# usb-current-meter-8x.net
KiCad netlist of a schematic drawn in EAGLE
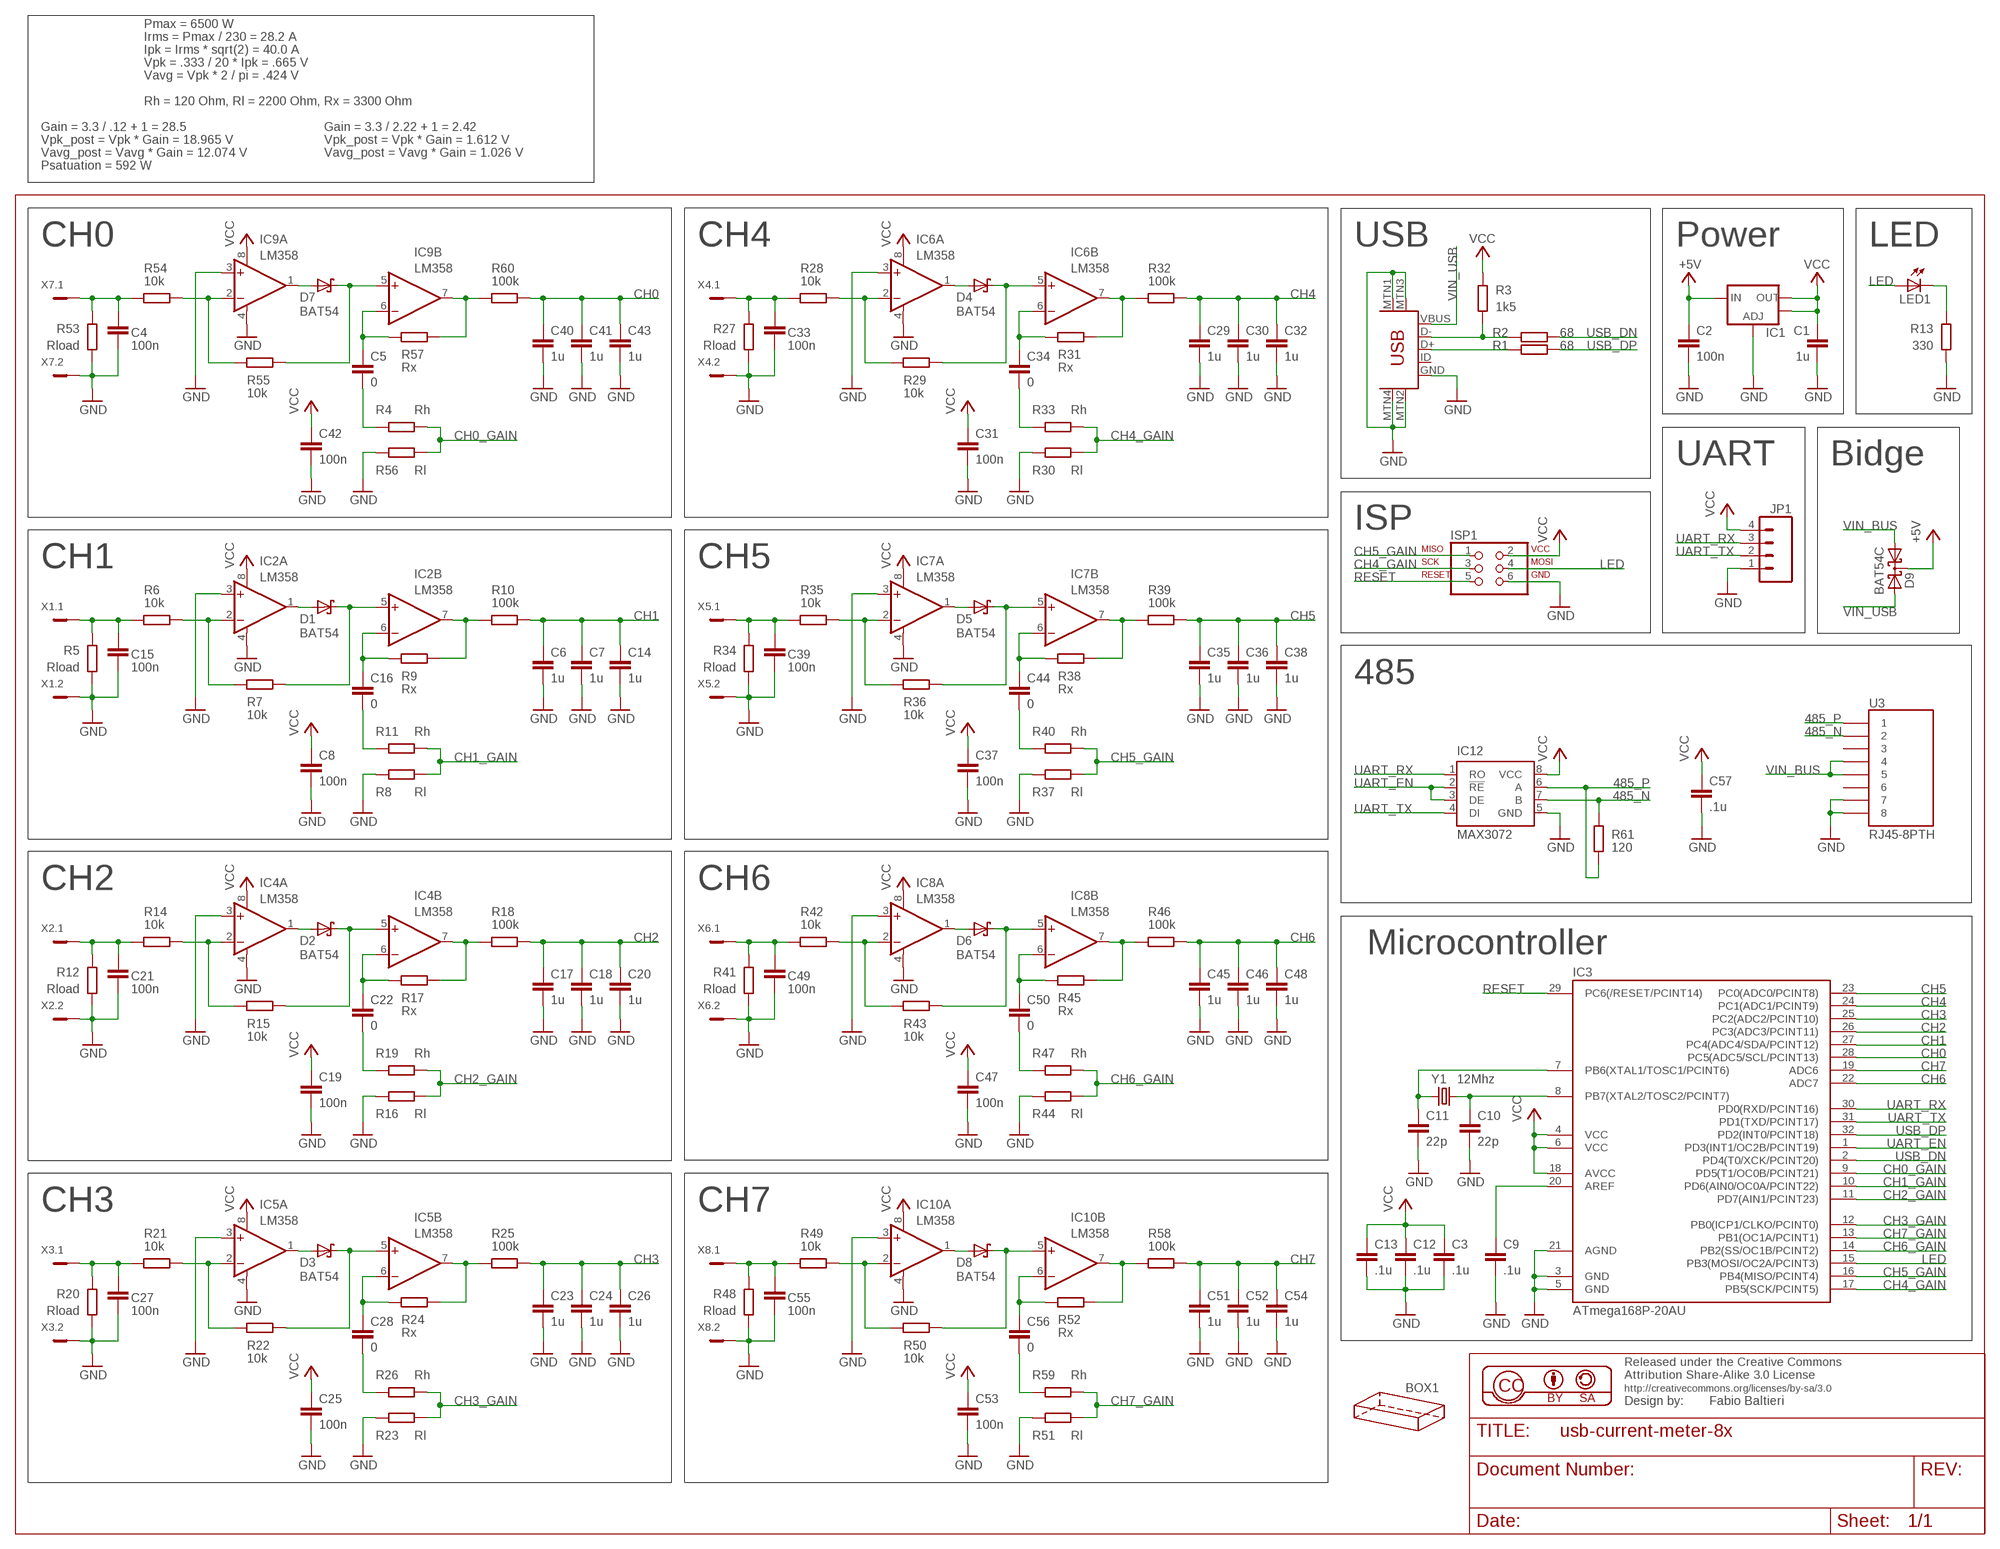
[diagram p0: schematic, sheet 1]

(export (version "E")
  (design (tool "Eeschema 10.0.6"))
  (components
    (comp (ref "BOX1")
      (value "HAMMOND-BOX-XXA")
      (footprint "eagle-import:1591XXA")
      (libsource (lib "eagle-import") (part "HAMMOND-BOX-XXA"))
    )
    (comp (ref "C1")
      (value "1u")
      (footprint "eagle-import:C0805")
      (libsource (lib "eagle-import") (part "C-EUC0805"))
    )
    (comp (ref "C2")
      (value "100n")
      (footprint "eagle-import:C0805")
      (libsource (lib "eagle-import") (part "C-EUC0805"))
    )
    (comp (ref "C3")
      (value ".1u")
      (footprint "eagle-import:C0805")
      (libsource (lib "eagle-import") (part "C-EUC0805"))
    )
    (comp (ref "C4")
      (value "100n")
      (footprint "eagle-import:C0805")
      (libsource (lib "eagle-import") (part "C-EUC0805"))
    )
    (comp (ref "C5")
      (value "0")
      (footprint "eagle-import:C0805")
      (libsource (lib "eagle-import") (part "C-EUC0805"))
    )
    (comp (ref "C6")
      (value "1u")
      (footprint "eagle-import:C0805")
      (libsource (lib "eagle-import") (part "C-EUC0805"))
    )
    (comp (ref "C7")
      (value "1u")
      (footprint "eagle-import:C0805")
      (libsource (lib "eagle-import") (part "C-EUC0805"))
    )
    (comp (ref "C8")
      (value "100n")
      (footprint "eagle-import:C0805")
      (libsource (lib "eagle-import") (part "C-EUC0805"))
    )
    (comp (ref "C9")
      (value ".1u")
      (footprint "eagle-import:C0805")
      (libsource (lib "eagle-import") (part "C-EUC0805"))
    )
    (comp (ref "C10")
      (value "22p")
      (footprint "eagle-import:C0805")
      (libsource (lib "eagle-import") (part "C-EUC0805"))
    )
    (comp (ref "C11")
      (value "22p")
      (footprint "eagle-import:C0805")
      (libsource (lib "eagle-import") (part "C-EUC0805"))
    )
    (comp (ref "C12")
      (value ".1u")
      (footprint "eagle-import:C0805")
      (libsource (lib "eagle-import") (part "C-EUC0805"))
    )
    (comp (ref "C13")
      (value ".1u")
      (footprint "eagle-import:C0805")
      (libsource (lib "eagle-import") (part "C-EUC0805"))
    )
    (comp (ref "C14")
      (value "1u")
      (footprint "eagle-import:C0805")
      (libsource (lib "eagle-import") (part "C-EUC0805"))
    )
    (comp (ref "C15")
      (value "100n")
      (footprint "eagle-import:C0805")
      (libsource (lib "eagle-import") (part "C-EUC0805"))
    )
    (comp (ref "C16")
      (value "0")
      (footprint "eagle-import:C0805")
      (libsource (lib "eagle-import") (part "C-EUC0805"))
    )
    (comp (ref "C17")
      (value "1u")
      (footprint "eagle-import:C0805")
      (libsource (lib "eagle-import") (part "C-EUC0805"))
    )
    (comp (ref "C18")
      (value "1u")
      (footprint "eagle-import:C0805")
      (libsource (lib "eagle-import") (part "C-EUC0805"))
    )
    (comp (ref "C19")
      (value "100n")
      (footprint "eagle-import:C0805")
      (libsource (lib "eagle-import") (part "C-EUC0805"))
    )
    (comp (ref "C20")
      (value "1u")
      (footprint "eagle-import:C0805")
      (libsource (lib "eagle-import") (part "C-EUC0805"))
    )
    (comp (ref "C21")
      (value "100n")
      (footprint "eagle-import:C0805")
      (libsource (lib "eagle-import") (part "C-EUC0805"))
    )
    (comp (ref "C22")
      (value "0")
      (footprint "eagle-import:C0805")
      (libsource (lib "eagle-import") (part "C-EUC0805"))
    )
    (comp (ref "C23")
      (value "1u")
      (footprint "eagle-import:C0805")
      (libsource (lib "eagle-import") (part "C-EUC0805"))
    )
    (comp (ref "C24")
      (value "1u")
      (footprint "eagle-import:C0805")
      (libsource (lib "eagle-import") (part "C-EUC0805"))
    )
    (comp (ref "C25")
      (value "100n")
      (footprint "eagle-import:C0805")
      (libsource (lib "eagle-import") (part "C-EUC0805"))
    )
    (comp (ref "C26")
      (value "1u")
      (footprint "eagle-import:C0805")
      (libsource (lib "eagle-import") (part "C-EUC0805"))
    )
    (comp (ref "C27")
      (value "100n")
      (footprint "eagle-import:C0805")
      (libsource (lib "eagle-import") (part "C-EUC0805"))
    )
    (comp (ref "C28")
      (value "0")
      (footprint "eagle-import:C0805")
      (libsource (lib "eagle-import") (part "C-EUC0805"))
    )
    (comp (ref "C29")
      (value "1u")
      (footprint "eagle-import:C0805")
      (libsource (lib "eagle-import") (part "C-EUC0805"))
    )
    (comp (ref "C30")
      (value "1u")
      (footprint "eagle-import:C0805")
      (libsource (lib "eagle-import") (part "C-EUC0805"))
    )
    (comp (ref "C31")
      (value "100n")
      (footprint "eagle-import:C0805")
      (libsource (lib "eagle-import") (part "C-EUC0805"))
    )
    (comp (ref "C32")
      (value "1u")
      (footprint "eagle-import:C0805")
      (libsource (lib "eagle-import") (part "C-EUC0805"))
    )
    (comp (ref "C33")
      (value "100n")
      (footprint "eagle-import:C0805")
      (libsource (lib "eagle-import") (part "C-EUC0805"))
    )
    (comp (ref "C34")
      (value "0")
      (footprint "eagle-import:C0805")
      (libsource (lib "eagle-import") (part "C-EUC0805"))
    )
    (comp (ref "C35")
      (value "1u")
      (footprint "eagle-import:C0805")
      (libsource (lib "eagle-import") (part "C-EUC0805"))
    )
    (comp (ref "C36")
      (value "1u")
      (footprint "eagle-import:C0805")
      (libsource (lib "eagle-import") (part "C-EUC0805"))
    )
    (comp (ref "C37")
      (value "100n")
      (footprint "eagle-import:C0805")
      (libsource (lib "eagle-import") (part "C-EUC0805"))
    )
    (comp (ref "C38")
      (value "1u")
      (footprint "eagle-import:C0805")
      (libsource (lib "eagle-import") (part "C-EUC0805"))
    )
    (comp (ref "C39")
      (value "100n")
      (footprint "eagle-import:C0805")
      (libsource (lib "eagle-import") (part "C-EUC0805"))
    )
    (comp (ref "C40")
      (value "1u")
      (footprint "eagle-import:C0805")
      (libsource (lib "eagle-import") (part "C-EUC0805"))
    )
    (comp (ref "C41")
      (value "1u")
      (footprint "eagle-import:C0805")
      (libsource (lib "eagle-import") (part "C-EUC0805"))
    )
    (comp (ref "C42")
      (value "100n")
      (footprint "eagle-import:C0805")
      (libsource (lib "eagle-import") (part "C-EUC0805"))
    )
    (comp (ref "C43")
      (value "1u")
      (footprint "eagle-import:C0805")
      (libsource (lib "eagle-import") (part "C-EUC0805"))
    )
    (comp (ref "C44")
      (value "0")
      (footprint "eagle-import:C0805")
      (libsource (lib "eagle-import") (part "C-EUC0805"))
    )
    (comp (ref "C45")
      (value "1u")
      (footprint "eagle-import:C0805")
      (libsource (lib "eagle-import") (part "C-EUC0805"))
    )
    (comp (ref "C46")
      (value "1u")
      (footprint "eagle-import:C0805")
      (libsource (lib "eagle-import") (part "C-EUC0805"))
    )
    (comp (ref "C47")
      (value "100n")
      (footprint "eagle-import:C0805")
      (libsource (lib "eagle-import") (part "C-EUC0805"))
    )
    (comp (ref "C48")
      (value "1u")
      (footprint "eagle-import:C0805")
      (libsource (lib "eagle-import") (part "C-EUC0805"))
    )
    (comp (ref "C49")
      (value "100n")
      (footprint "eagle-import:C0805")
      (libsource (lib "eagle-import") (part "C-EUC0805"))
    )
    (comp (ref "C50")
      (value "0")
      (footprint "eagle-import:C0805")
      (libsource (lib "eagle-import") (part "C-EUC0805"))
    )
    (comp (ref "C51")
      (value "1u")
      (footprint "eagle-import:C0805")
      (libsource (lib "eagle-import") (part "C-EUC0805"))
    )
    (comp (ref "C52")
      (value "1u")
      (footprint "eagle-import:C0805")
      (libsource (lib "eagle-import") (part "C-EUC0805"))
    )
    (comp (ref "C53")
      (value "100n")
      (footprint "eagle-import:C0805")
      (libsource (lib "eagle-import") (part "C-EUC0805"))
    )
    (comp (ref "C54")
      (value "1u")
      (footprint "eagle-import:C0805")
      (libsource (lib "eagle-import") (part "C-EUC0805"))
    )
    (comp (ref "C55")
      (value "100n")
      (footprint "eagle-import:C0805")
      (libsource (lib "eagle-import") (part "C-EUC0805"))
    )
    (comp (ref "C56")
      (value "0")
      (footprint "eagle-import:C0805")
      (libsource (lib "eagle-import") (part "C-EUC0805"))
    )
    (comp (ref "C57")
      (value ".1u")
      (footprint "eagle-import:C0805")
      (libsource (lib "eagle-import") (part "C-EUC0805"))
    )
    (comp (ref "D1")
      (value "BAT54")
      (footprint "eagle-import:SOT23")
      (libsource (lib "eagle-import") (part "BAT54"))
    )
    (comp (ref "D2")
      (value "BAT54")
      (footprint "eagle-import:SOT23")
      (libsource (lib "eagle-import") (part "BAT54"))
    )
    (comp (ref "D3")
      (value "BAT54")
      (footprint "eagle-import:SOT23")
      (libsource (lib "eagle-import") (part "BAT54"))
    )
    (comp (ref "D4")
      (value "BAT54")
      (footprint "eagle-import:SOT23")
      (libsource (lib "eagle-import") (part "BAT54"))
    )
    (comp (ref "D5")
      (value "BAT54")
      (footprint "eagle-import:SOT23")
      (libsource (lib "eagle-import") (part "BAT54"))
    )
    (comp (ref "D6")
      (value "BAT54")
      (footprint "eagle-import:SOT23")
      (libsource (lib "eagle-import") (part "BAT54"))
    )
    (comp (ref "D7")
      (value "BAT54")
      (footprint "eagle-import:SOT23")
      (libsource (lib "eagle-import") (part "BAT54"))
    )
    (comp (ref "D8")
      (value "BAT54")
      (footprint "eagle-import:SOT23")
      (libsource (lib "eagle-import") (part "BAT54"))
    )
    (comp (ref "D9")
      (value "BAT54C")
      (footprint "eagle-import:SOT23")
      (libsource (lib "eagle-import") (part "BAT54C"))
    )
    (comp (ref "IC1")
      (value "V_REG_LM1117SOT223")
      (footprint "eagle-import:SOT223")
      (libsource (lib "eagle-import") (part "V_REG_LM1117SOT223"))
    )
    (comp (ref "IC2")
      (value "LM358")
      (footprint "eagle-import:SO08")
      (fields (field (name "MF") "TEXAS INSTRUMENTS") (field (name "MPN") "OPA2234U"))
      (libsource (lib "eagle-import") (part "OPA2234U"))
    )
    (comp (ref "IC3")
      (value "ATmega168P-20AU")
      (footprint "eagle-import:TQFP32-08")
      (libsource (lib "eagle-import") (part "MEGA48/88/168-AU"))
    )
    (comp (ref "IC4")
      (value "LM358")
      (footprint "eagle-import:SO08")
      (fields (field (name "MF") "TEXAS INSTRUMENTS") (field (name "MPN") "OPA2234U"))
      (libsource (lib "eagle-import") (part "OPA2234U"))
    )
    (comp (ref "IC5")
      (value "LM358")
      (footprint "eagle-import:SO08")
      (fields (field (name "MF") "TEXAS INSTRUMENTS") (field (name "MPN") "OPA2234U"))
      (libsource (lib "eagle-import") (part "OPA2234U"))
    )
    (comp (ref "IC6")
      (value "LM358")
      (footprint "eagle-import:SO08")
      (fields (field (name "MF") "TEXAS INSTRUMENTS") (field (name "MPN") "OPA2234U"))
      (libsource (lib "eagle-import") (part "OPA2234U"))
    )
    (comp (ref "IC7")
      (value "LM358")
      (footprint "eagle-import:SO08")
      (fields (field (name "MF") "TEXAS INSTRUMENTS") (field (name "MPN") "OPA2234U"))
      (libsource (lib "eagle-import") (part "OPA2234U"))
    )
    (comp (ref "IC8")
      (value "LM358")
      (footprint "eagle-import:SO08")
      (fields (field (name "MF") "TEXAS INSTRUMENTS") (field (name "MPN") "OPA2234U"))
      (libsource (lib "eagle-import") (part "OPA2234U"))
    )
    (comp (ref "IC9")
      (value "LM358")
      (footprint "eagle-import:SO08")
      (fields (field (name "MF") "TEXAS INSTRUMENTS") (field (name "MPN") "OPA2234U"))
      (libsource (lib "eagle-import") (part "OPA2234U"))
    )
    (comp (ref "IC10")
      (value "LM358")
      (footprint "eagle-import:SO08")
      (fields (field (name "MF") "TEXAS INSTRUMENTS") (field (name "MPN") "OPA2234U"))
      (libsource (lib "eagle-import") (part "OPA2234U"))
    )
    (comp (ref "IC12")
      (value "MAX3072")
      (footprint "eagle-import:SOIC8")
      (libsource (lib "eagle-import") (part "LTC485S"))
    )
    (comp (ref "ISP1")
      (value "ISP-AVR910PTH")
      (footprint "eagle-import:2X03")
      (libsource (lib "eagle-import") (part "ISP-AVR910PTH"))
    )
    (comp (ref "JP1")
      (value "M04PTH")
      (footprint "eagle-import:1X04")
      (libsource (lib "eagle-import") (part "M04PTH"))
    )
    (comp (ref "LED1")
      (value "LEDSML0805")
      (footprint "eagle-import:SML0805")
      (libsource (lib "eagle-import") (part "LEDSML0805"))
    )
    (comp (ref "R1")
      (value "68")
      (footprint "eagle-import:R0603")
      (libsource (lib "eagle-import") (part "R-EU_R0603"))
    )
    (comp (ref "R2")
      (value "68")
      (footprint "eagle-import:R0603")
      (libsource (lib "eagle-import") (part "R-EU_R0603"))
    )
    (comp (ref "R3")
      (value "1k5")
      (footprint "eagle-import:R0603")
      (libsource (lib "eagle-import") (part "R-EU_R0603"))
    )
    (comp (ref "R4")
      (value "Rh")
      (footprint "eagle-import:R0603")
      (libsource (lib "eagle-import") (part "R-EU_R0603"))
    )
    (comp (ref "R5")
      (value "Rload")
      (footprint "eagle-import:R0805")
      (libsource (lib "eagle-import") (part "R-EU_R0805"))
    )
    (comp (ref "R6")
      (value "10k")
      (footprint "eagle-import:R0603")
      (libsource (lib "eagle-import") (part "R-EU_R0603"))
    )
    (comp (ref "R7")
      (value "10k")
      (footprint "eagle-import:R0603")
      (libsource (lib "eagle-import") (part "R-EU_R0603"))
    )
    (comp (ref "R8")
      (value "Rl")
      (footprint "eagle-import:R0603")
      (libsource (lib "eagle-import") (part "R-EU_R0603"))
    )
    (comp (ref "R9")
      (value "Rx")
      (footprint "eagle-import:R0603")
      (libsource (lib "eagle-import") (part "R-EU_R0603"))
    )
    (comp (ref "R10")
      (value "100k")
      (footprint "eagle-import:R0603")
      (libsource (lib "eagle-import") (part "R-EU_R0603"))
    )
    (comp (ref "R11")
      (value "Rh")
      (footprint "eagle-import:R0603")
      (libsource (lib "eagle-import") (part "R-EU_R0603"))
    )
    (comp (ref "R12")
      (value "Rload")
      (footprint "eagle-import:R0805")
      (libsource (lib "eagle-import") (part "R-EU_R0805"))
    )
    (comp (ref "R13")
      (value "330")
      (footprint "eagle-import:R0603")
      (libsource (lib "eagle-import") (part "R-EU_R0603"))
    )
    (comp (ref "R14")
      (value "10k")
      (footprint "eagle-import:R0603")
      (libsource (lib "eagle-import") (part "R-EU_R0603"))
    )
    (comp (ref "R15")
      (value "10k")
      (footprint "eagle-import:R0603")
      (libsource (lib "eagle-import") (part "R-EU_R0603"))
    )
    (comp (ref "R16")
      (value "Rl")
      (footprint "eagle-import:R0603")
      (libsource (lib "eagle-import") (part "R-EU_R0603"))
    )
    (comp (ref "R17")
      (value "Rx")
      (footprint "eagle-import:R0603")
      (libsource (lib "eagle-import") (part "R-EU_R0603"))
    )
    (comp (ref "R18")
      (value "100k")
      (footprint "eagle-import:R0603")
      (libsource (lib "eagle-import") (part "R-EU_R0603"))
    )
    (comp (ref "R19")
      (value "Rh")
      (footprint "eagle-import:R0603")
      (libsource (lib "eagle-import") (part "R-EU_R0603"))
    )
    (comp (ref "R20")
      (value "Rload")
      (footprint "eagle-import:R0805")
      (libsource (lib "eagle-import") (part "R-EU_R0805"))
    )
    (comp (ref "R21")
      (value "10k")
      (footprint "eagle-import:R0603")
      (libsource (lib "eagle-import") (part "R-EU_R0603"))
    )
    (comp (ref "R22")
      (value "10k")
      (footprint "eagle-import:R0603")
      (libsource (lib "eagle-import") (part "R-EU_R0603"))
    )
    (comp (ref "R23")
      (value "Rl")
      (footprint "eagle-import:R0603")
      (libsource (lib "eagle-import") (part "R-EU_R0603"))
    )
    (comp (ref "R24")
      (value "Rx")
      (footprint "eagle-import:R0603")
      (libsource (lib "eagle-import") (part "R-EU_R0603"))
    )
    (comp (ref "R25")
      (value "100k")
      (footprint "eagle-import:R0603")
      (libsource (lib "eagle-import") (part "R-EU_R0603"))
    )
    (comp (ref "R26")
      (value "Rh")
      (footprint "eagle-import:R0603")
      (libsource (lib "eagle-import") (part "R-EU_R0603"))
    )
    (comp (ref "R27")
      (value "Rload")
      (footprint "eagle-import:R0805")
      (libsource (lib "eagle-import") (part "R-EU_R0805"))
    )
    (comp (ref "R28")
      (value "10k")
      (footprint "eagle-import:R0603")
      (libsource (lib "eagle-import") (part "R-EU_R0603"))
    )
    (comp (ref "R29")
      (value "10k")
      (footprint "eagle-import:R0603")
      (libsource (lib "eagle-import") (part "R-EU_R0603"))
    )
    (comp (ref "R30")
      (value "Rl")
      (footprint "eagle-import:R0603")
      (libsource (lib "eagle-import") (part "R-EU_R0603"))
    )
    (comp (ref "R31")
      (value "Rx")
      (footprint "eagle-import:R0603")
      (libsource (lib "eagle-import") (part "R-EU_R0603"))
    )
    (comp (ref "R32")
      (value "100k")
      (footprint "eagle-import:R0603")
      (libsource (lib "eagle-import") (part "R-EU_R0603"))
    )
    (comp (ref "R33")
      (value "Rh")
      (footprint "eagle-import:R0603")
      (libsource (lib "eagle-import") (part "R-EU_R0603"))
    )
    (comp (ref "R34")
      (value "Rload")
      (footprint "eagle-import:R0805")
      (libsource (lib "eagle-import") (part "R-EU_R0805"))
    )
    (comp (ref "R35")
      (value "10k")
      (footprint "eagle-import:R0603")
      (libsource (lib "eagle-import") (part "R-EU_R0603"))
    )
    (comp (ref "R36")
      (value "10k")
      (footprint "eagle-import:R0603")
      (libsource (lib "eagle-import") (part "R-EU_R0603"))
    )
    (comp (ref "R37")
      (value "Rl")
      (footprint "eagle-import:R0603")
      (libsource (lib "eagle-import") (part "R-EU_R0603"))
    )
    (comp (ref "R38")
      (value "Rx")
      (footprint "eagle-import:R0603")
      (libsource (lib "eagle-import") (part "R-EU_R0603"))
    )
    (comp (ref "R39")
      (value "100k")
      (footprint "eagle-import:R0603")
      (libsource (lib "eagle-import") (part "R-EU_R0603"))
    )
    (comp (ref "R40")
      (value "Rh")
      (footprint "eagle-import:R0603")
      (libsource (lib "eagle-import") (part "R-EU_R0603"))
    )
    (comp (ref "R41")
      (value "Rload")
      (footprint "eagle-import:R0805")
      (libsource (lib "eagle-import") (part "R-EU_R0805"))
    )
    (comp (ref "R42")
      (value "10k")
      (footprint "eagle-import:R0603")
      (libsource (lib "eagle-import") (part "R-EU_R0603"))
    )
    (comp (ref "R43")
      (value "10k")
      (footprint "eagle-import:R0603")
      (libsource (lib "eagle-import") (part "R-EU_R0603"))
    )
    (comp (ref "R44")
      (value "Rl")
      (footprint "eagle-import:R0603")
      (libsource (lib "eagle-import") (part "R-EU_R0603"))
    )
    (comp (ref "R45")
      (value "Rx")
      (footprint "eagle-import:R0603")
      (libsource (lib "eagle-import") (part "R-EU_R0603"))
    )
    (comp (ref "R46")
      (value "100k")
      (footprint "eagle-import:R0603")
      (libsource (lib "eagle-import") (part "R-EU_R0603"))
    )
    (comp (ref "R47")
      (value "Rh")
      (footprint "eagle-import:R0603")
      (libsource (lib "eagle-import") (part "R-EU_R0603"))
    )
    (comp (ref "R48")
      (value "Rload")
      (footprint "eagle-import:R0805")
      (libsource (lib "eagle-import") (part "R-EU_R0805"))
    )
    (comp (ref "R49")
      (value "10k")
      (footprint "eagle-import:R0603")
      (libsource (lib "eagle-import") (part "R-EU_R0603"))
    )
    (comp (ref "R50")
      (value "10k")
      (footprint "eagle-import:R0603")
      (libsource (lib "eagle-import") (part "R-EU_R0603"))
    )
    (comp (ref "R51")
      (value "Rl")
      (footprint "eagle-import:R0603")
      (libsource (lib "eagle-import") (part "R-EU_R0603"))
    )
    (comp (ref "R52")
      (value "Rx")
      (footprint "eagle-import:R0603")
      (libsource (lib "eagle-import") (part "R-EU_R0603"))
    )
    (comp (ref "R53")
      (value "Rload")
      (footprint "eagle-import:R0805")
      (libsource (lib "eagle-import") (part "R-EU_R0805"))
    )
    (comp (ref "R54")
      (value "10k")
      (footprint "eagle-import:R0603")
      (libsource (lib "eagle-import") (part "R-EU_R0603"))
    )
    (comp (ref "R55")
      (value "10k")
      (footprint "eagle-import:R0603")
      (libsource (lib "eagle-import") (part "R-EU_R0603"))
    )
    (comp (ref "R56")
      (value "Rl")
      (footprint "eagle-import:R0603")
      (libsource (lib "eagle-import") (part "R-EU_R0603"))
    )
    (comp (ref "R57")
      (value "Rx")
      (footprint "eagle-import:R0603")
      (libsource (lib "eagle-import") (part "R-EU_R0603"))
    )
    (comp (ref "R58")
      (value "100k")
      (footprint "eagle-import:R0603")
      (libsource (lib "eagle-import") (part "R-EU_R0603"))
    )
    (comp (ref "R59")
      (value "Rh")
      (footprint "eagle-import:R0603")
      (libsource (lib "eagle-import") (part "R-EU_R0603"))
    )
    (comp (ref "R60")
      (value "100k")
      (footprint "eagle-import:R0603")
      (libsource (lib "eagle-import") (part "R-EU_R0603"))
    )
    (comp (ref "R61")
      (value "120")
      (footprint "eagle-import:R0603")
      (libsource (lib "eagle-import") (part "R-EU_R0603"))
    )
    (comp (ref "U$1")
      (value "USB-MINIB-5PIN")
      (footprint "eagle-import:USB-MINIB")
      (libsource (lib "eagle-import") (part "USB-MINIB-5PIN"))
    )
    (comp (ref "U$2")
      (value "Fabio Baltieri")
      (footprint "eagle-import:CREATIVE_COMMONS")
      (libsource (lib "eagle-import") (part "CREATIVE_COMMONS"))
    )
    (comp (ref "U3")
      (value "RJ45-8PTH")
      (footprint "eagle-import:RJ45-8")
      (libsource (lib "eagle-import") (part "RJ45-8PTH"))
    )
    (comp (ref "X1")
      (value "MC2")
      (footprint "eagle-import:MC2")
      (libsource (lib "eagle-import") (part "MC2"))
    )
    (comp (ref "X2")
      (value "MC2")
      (footprint "eagle-import:MC2")
      (libsource (lib "eagle-import") (part "MC2"))
    )
    (comp (ref "X3")
      (value "MC2")
      (footprint "eagle-import:MC2")
      (libsource (lib "eagle-import") (part "MC2"))
    )
    (comp (ref "X4")
      (value "MC2")
      (footprint "eagle-import:MC2")
      (libsource (lib "eagle-import") (part "MC2"))
    )
    (comp (ref "X5")
      (value "MC2")
      (footprint "eagle-import:MC2")
      (libsource (lib "eagle-import") (part "MC2"))
    )
    (comp (ref "X6")
      (value "MC2")
      (footprint "eagle-import:MC2")
      (libsource (lib "eagle-import") (part "MC2"))
    )
    (comp (ref "X7")
      (value "MC2")
      (footprint "eagle-import:MC2")
      (libsource (lib "eagle-import") (part "MC2"))
    )
    (comp (ref "X8")
      (value "MC2")
      (footprint "eagle-import:MC2")
      (libsource (lib "eagle-import") (part "MC2"))
    )
    (comp (ref "Y1")
      (value "12Mhz")
      (footprint "eagle-import:HC49U-V")
      (libsource (lib "eagle-import") (part "CRYSTALHC49UV"))
    )
  )
  (nets
    (net (code "1") (name "+5V") (class "Default")
      (node (ref "C2") (pin "1") (pinfunction "1_1") (pintype "passive"))
      (node (ref "D9") (pin "3") (pinfunction "CC_3") (pintype "passive"))
      (node (ref "IC1") (pin "3") (pinfunction "IN_3") (pintype "input"))
    )
    (net (code "2") (name "/485_N") (class "Default")
      (node (ref "IC12") (pin "7") (pinfunction "B_7") (pintype "bidirectional"))
      (node (ref "R61") (pin "1") (pinfunction "1_1") (pintype "passive"))
      (node (ref "U3") (pin "2") (pinfunction "2_2") (pintype "bidirectional"))
    )
    (net (code "3") (name "/485_P") (class "Default")
      (node (ref "IC12") (pin "6") (pinfunction "A_6") (pintype "bidirectional"))
      (node (ref "R61") (pin "2") (pinfunction "2_2") (pintype "passive"))
      (node (ref "U3") (pin "1") (pinfunction "1_1") (pintype "bidirectional"))
    )
    (net (code "4") (name "/CH0") (class "Default")
      (node (ref "C40") (pin "1") (pinfunction "1_1") (pintype "passive"))
      (node (ref "C41") (pin "1") (pinfunction "1_1") (pintype "passive"))
      (node (ref "C43") (pin "1") (pinfunction "1_1") (pintype "passive"))
      (node (ref "IC3") (pin "28") (pinfunction "PC5(ADC5/SCL/PCINT13)_28") (pintype "bidirectional"))
      (node (ref "R60") (pin "2") (pinfunction "2_2") (pintype "passive"))
    )
    (net (code "5") (name "/CH0_GAIN") (class "Default")
      (node (ref "IC3") (pin "9") (pinfunction "PD5(T1/OC0B/PCINT21)_9") (pintype "bidirectional"))
      (node (ref "R4") (pin "1") (pinfunction "1_1") (pintype "passive"))
      (node (ref "R56") (pin "2") (pinfunction "2_2") (pintype "passive"))
    )
    (net (code "6") (name "/CH1") (class "Default")
      (node (ref "C14") (pin "1") (pinfunction "1_1") (pintype "passive"))
      (node (ref "C6") (pin "1") (pinfunction "1_1") (pintype "passive"))
      (node (ref "C7") (pin "1") (pinfunction "1_1") (pintype "passive"))
      (node (ref "IC3") (pin "27") (pinfunction "PC4(ADC4/SDA/PCINT12)_27") (pintype "bidirectional"))
      (node (ref "R10") (pin "2") (pinfunction "2_2") (pintype "passive"))
    )
    (net (code "7") (name "/CH1_GAIN") (class "Default")
      (node (ref "IC3") (pin "10") (pinfunction "PD6(AIN0/OC0A/PCINT22)_10") (pintype "bidirectional"))
      (node (ref "R11") (pin "1") (pinfunction "1_1") (pintype "passive"))
      (node (ref "R8") (pin "2") (pinfunction "2_2") (pintype "passive"))
    )
    (net (code "8") (name "/CH2") (class "Default")
      (node (ref "C17") (pin "1") (pinfunction "1_1") (pintype "passive"))
      (node (ref "C18") (pin "1") (pinfunction "1_1") (pintype "passive"))
      (node (ref "C20") (pin "1") (pinfunction "1_1") (pintype "passive"))
      (node (ref "IC3") (pin "26") (pinfunction "PC3(ADC3/PCINT11)_26") (pintype "bidirectional"))
      (node (ref "R18") (pin "2") (pinfunction "2_2") (pintype "passive"))
    )
    (net (code "9") (name "/CH2_GAIN") (class "Default")
      (node (ref "IC3") (pin "11") (pinfunction "PD7(AIN1/PCINT23)_11") (pintype "bidirectional"))
      (node (ref "R16") (pin "2") (pinfunction "2_2") (pintype "passive"))
      (node (ref "R19") (pin "1") (pinfunction "1_1") (pintype "passive"))
    )
    (net (code "10") (name "/CH3") (class "Default")
      (node (ref "C23") (pin "1") (pinfunction "1_1") (pintype "passive"))
      (node (ref "C24") (pin "1") (pinfunction "1_1") (pintype "passive"))
      (node (ref "C26") (pin "1") (pinfunction "1_1") (pintype "passive"))
      (node (ref "IC3") (pin "25") (pinfunction "PC2(ADC2/PCINT10)_25") (pintype "bidirectional"))
      (node (ref "R25") (pin "2") (pinfunction "2_2") (pintype "passive"))
    )
    (net (code "11") (name "/CH3_GAIN") (class "Default")
      (node (ref "IC3") (pin "12") (pinfunction "PB0(ICP1/CLKO/PCINT0)_12") (pintype "bidirectional"))
      (node (ref "R23") (pin "2") (pinfunction "2_2") (pintype "passive"))
      (node (ref "R26") (pin "1") (pinfunction "1_1") (pintype "passive"))
    )
    (net (code "12") (name "/CH4") (class "Default")
      (node (ref "C29") (pin "1") (pinfunction "1_1") (pintype "passive"))
      (node (ref "C30") (pin "1") (pinfunction "1_1") (pintype "passive"))
      (node (ref "C32") (pin "1") (pinfunction "1_1") (pintype "passive"))
      (node (ref "IC3") (pin "24") (pinfunction "PC1(ADC1/PCINT9)_24") (pintype "bidirectional"))
      (node (ref "R32") (pin "2") (pinfunction "2_2") (pintype "passive"))
    )
    (net (code "13") (name "/CH4_GAIN") (class "Default")
      (node (ref "IC3") (pin "17") (pinfunction "PB5(SCK/PCINT5)_17") (pintype "bidirectional"))
      (node (ref "ISP1") (pin "3") (pinfunction "3_3") (pintype "passive"))
      (node (ref "R30") (pin "2") (pinfunction "2_2") (pintype "passive"))
      (node (ref "R33") (pin "1") (pinfunction "1_1") (pintype "passive"))
    )
    (net (code "14") (name "/CH5") (class "Default")
      (node (ref "C35") (pin "1") (pinfunction "1_1") (pintype "passive"))
      (node (ref "C36") (pin "1") (pinfunction "1_1") (pintype "passive"))
      (node (ref "C38") (pin "1") (pinfunction "1_1") (pintype "passive"))
      (node (ref "IC3") (pin "23") (pinfunction "PC0(ADC0/PCINT8)_23") (pintype "bidirectional"))
      (node (ref "R39") (pin "2") (pinfunction "2_2") (pintype "passive"))
    )
    (net (code "15") (name "/CH5_GAIN") (class "Default")
      (node (ref "IC3") (pin "16") (pinfunction "PB4(MISO/PCINT4)_16") (pintype "bidirectional"))
      (node (ref "ISP1") (pin "1") (pinfunction "1_1") (pintype "passive"))
      (node (ref "R37") (pin "2") (pinfunction "2_2") (pintype "passive"))
      (node (ref "R40") (pin "1") (pinfunction "1_1") (pintype "passive"))
    )
    (net (code "16") (name "/CH6") (class "Default")
      (node (ref "C45") (pin "1") (pinfunction "1_1") (pintype "passive"))
      (node (ref "C46") (pin "1") (pinfunction "1_1") (pintype "passive"))
      (node (ref "C48") (pin "1") (pinfunction "1_1") (pintype "passive"))
      (node (ref "IC3") (pin "22") (pinfunction "ADC7_22") (pintype "passive"))
      (node (ref "R46") (pin "2") (pinfunction "2_2") (pintype "passive"))
    )
    (net (code "17") (name "/CH6_GAIN") (class "Default")
      (node (ref "IC3") (pin "14") (pinfunction "PB2(SS/OC1B/PCINT2)_14") (pintype "bidirectional"))
      (node (ref "R44") (pin "2") (pinfunction "2_2") (pintype "passive"))
      (node (ref "R47") (pin "1") (pinfunction "1_1") (pintype "passive"))
    )
    (net (code "18") (name "/CH7") (class "Default")
      (node (ref "C51") (pin "1") (pinfunction "1_1") (pintype "passive"))
      (node (ref "C52") (pin "1") (pinfunction "1_1") (pintype "passive"))
      (node (ref "C54") (pin "1") (pinfunction "1_1") (pintype "passive"))
      (node (ref "IC3") (pin "19") (pinfunction "ADC6_19") (pintype "passive"))
      (node (ref "R58") (pin "2") (pinfunction "2_2") (pintype "passive"))
    )
    (net (code "19") (name "/CH7_GAIN") (class "Default")
      (node (ref "IC3") (pin "13") (pinfunction "PB1(OC1A/PCINT1)_13") (pintype "bidirectional"))
      (node (ref "R51") (pin "2") (pinfunction "2_2") (pintype "passive"))
      (node (ref "R59") (pin "1") (pinfunction "1_1") (pintype "passive"))
    )
    (net (code "20") (name "/LED") (class "Default")
      (node (ref "IC3") (pin "15") (pinfunction "PB3(MOSI/OC2A/PCINT3)_15") (pintype "bidirectional"))
      (node (ref "ISP1") (pin "4") (pinfunction "4_4") (pintype "passive"))
      (node (ref "LED1") (pin "A") (pinfunction "A_A") (pintype "passive"))
    )
    (net (code "21") (name "/RESET") (class "Default")
      (node (ref "IC3") (pin "29") (pinfunction "PC6(/RESET/PCINT14)_29") (pintype "bidirectional"))
      (node (ref "ISP1") (pin "5") (pinfunction "5_5") (pintype "passive"))
    )
    (net (code "22") (name "/UART_EN") (class "Default")
      (node (ref "IC12") (pin "2") (pinfunction "~{RE}_2") (pintype "input"))
      (node (ref "IC12") (pin "3") (pinfunction "DE_3") (pintype "input"))
      (node (ref "IC3") (pin "1") (pinfunction "PD3(INT1/OC2B/PCINT19)_1") (pintype "bidirectional"))
    )
    (net (code "23") (name "/UART_RX") (class "Default")
      (node (ref "IC12") (pin "1") (pinfunction "RO_1") (pintype "output"))
      (node (ref "IC3") (pin "30") (pinfunction "PD0(RXD/PCINT16)_30") (pintype "bidirectional"))
      (node (ref "JP1") (pin "3") (pinfunction "3_3") (pintype "passive"))
    )
    (net (code "24") (name "/UART_TX") (class "Default")
      (node (ref "IC12") (pin "4") (pinfunction "DI_4") (pintype "input"))
      (node (ref "IC3") (pin "31") (pinfunction "PD1(TXD/PCINT17)_31") (pintype "bidirectional"))
      (node (ref "JP1") (pin "2") (pinfunction "2_2") (pintype "passive"))
    )
    (net (code "25") (name "/USB_DN") (class "Default")
      (node (ref "IC3") (pin "2") (pinfunction "PD4(T0/XCK/PCINT20)_2") (pintype "bidirectional"))
      (node (ref "R2") (pin "2") (pinfunction "2_2") (pintype "passive"))
    )
    (net (code "26") (name "/USB_DP") (class "Default")
      (node (ref "IC3") (pin "32") (pinfunction "PD2(INT0/PCINT18)_32") (pintype "bidirectional"))
      (node (ref "R1") (pin "2") (pinfunction "2_2") (pintype "passive"))
    )
    (net (code "27") (name "/VIN_BUS") (class "Default")
      (node (ref "D9") (pin "1") (pinfunction "A1_1") (pintype "passive"))
      (node (ref "U3") (pin "4") (pinfunction "4_4") (pintype "bidirectional"))
      (node (ref "U3") (pin "5") (pinfunction "5_5") (pintype "bidirectional"))
    )
    (net (code "28") (name "/VIN_USB") (class "Default")
      (node (ref "D9") (pin "2") (pinfunction "A2_2") (pintype "passive"))
      (node (ref "U$1") (pin "VBUS") (pinfunction "VBUS_VBUS") (pintype "bidirectional"))
    )
    (net (code "29") (name "GND") (class "Default")
      (node (ref "C1") (pin "2") (pinfunction "2_2") (pintype "passive"))
      (node (ref "C10") (pin "2") (pinfunction "2_2") (pintype "passive"))
      (node (ref "C11") (pin "2") (pinfunction "2_2") (pintype "passive"))
      (node (ref "C12") (pin "2") (pinfunction "2_2") (pintype "passive"))
      (node (ref "C13") (pin "2") (pinfunction "2_2") (pintype "passive"))
      (node (ref "C14") (pin "2") (pinfunction "2_2") (pintype "passive"))
      (node (ref "C15") (pin "2") (pinfunction "2_2") (pintype "passive"))
      (node (ref "C17") (pin "2") (pinfunction "2_2") (pintype "passive"))
      (node (ref "C18") (pin "2") (pinfunction "2_2") (pintype "passive"))
      (node (ref "C19") (pin "2") (pinfunction "2_2") (pintype "passive"))
      (node (ref "C2") (pin "2") (pinfunction "2_2") (pintype "passive"))
      (node (ref "C20") (pin "2") (pinfunction "2_2") (pintype "passive"))
      (node (ref "C21") (pin "2") (pinfunction "2_2") (pintype "passive"))
      (node (ref "C23") (pin "2") (pinfunction "2_2") (pintype "passive"))
      (node (ref "C24") (pin "2") (pinfunction "2_2") (pintype "passive"))
      (node (ref "C25") (pin "2") (pinfunction "2_2") (pintype "passive"))
      (node (ref "C26") (pin "2") (pinfunction "2_2") (pintype "passive"))
      (node (ref "C27") (pin "2") (pinfunction "2_2") (pintype "passive"))
      (node (ref "C29") (pin "2") (pinfunction "2_2") (pintype "passive"))
      (node (ref "C3") (pin "2") (pinfunction "2_2") (pintype "passive"))
      (node (ref "C30") (pin "2") (pinfunction "2_2") (pintype "passive"))
      (node (ref "C31") (pin "2") (pinfunction "2_2") (pintype "passive"))
      (node (ref "C32") (pin "2") (pinfunction "2_2") (pintype "passive"))
      (node (ref "C33") (pin "2") (pinfunction "2_2") (pintype "passive"))
      (node (ref "C35") (pin "2") (pinfunction "2_2") (pintype "passive"))
      (node (ref "C36") (pin "2") (pinfunction "2_2") (pintype "passive"))
      (node (ref "C37") (pin "2") (pinfunction "2_2") (pintype "passive"))
      (node (ref "C38") (pin "2") (pinfunction "2_2") (pintype "passive"))
      (node (ref "C39") (pin "2") (pinfunction "2_2") (pintype "passive"))
      (node (ref "C4") (pin "2") (pinfunction "2_2") (pintype "passive"))
      (node (ref "C40") (pin "2") (pinfunction "2_2") (pintype "passive"))
      (node (ref "C41") (pin "2") (pinfunction "2_2") (pintype "passive"))
      (node (ref "C42") (pin "2") (pinfunction "2_2") (pintype "passive"))
      (node (ref "C43") (pin "2") (pinfunction "2_2") (pintype "passive"))
      (node (ref "C45") (pin "2") (pinfunction "2_2") (pintype "passive"))
      (node (ref "C46") (pin "2") (pinfunction "2_2") (pintype "passive"))
      (node (ref "C47") (pin "2") (pinfunction "2_2") (pintype "passive"))
      (node (ref "C48") (pin "2") (pinfunction "2_2") (pintype "passive"))
      (node (ref "C49") (pin "2") (pinfunction "2_2") (pintype "passive"))
      (node (ref "C51") (pin "2") (pinfunction "2_2") (pintype "passive"))
      (node (ref "C52") (pin "2") (pinfunction "2_2") (pintype "passive"))
      (node (ref "C53") (pin "2") (pinfunction "2_2") (pintype "passive"))
      (node (ref "C54") (pin "2") (pinfunction "2_2") (pintype "passive"))
      (node (ref "C55") (pin "2") (pinfunction "2_2") (pintype "passive"))
      (node (ref "C57") (pin "2") (pinfunction "2_2") (pintype "passive"))
      (node (ref "C6") (pin "2") (pinfunction "2_2") (pintype "passive"))
      (node (ref "C7") (pin "2") (pinfunction "2_2") (pintype "passive"))
      (node (ref "C8") (pin "2") (pinfunction "2_2") (pintype "passive"))
      (node (ref "C9") (pin "2") (pinfunction "2_2") (pintype "passive"))
      (node (ref "IC1") (pin "1") (pinfunction "ADJ_1") (pintype "input"))
      (node (ref "IC10") (pin "3") (pinfunction "+IN_3") (pintype "input"))
      (node (ref "IC10") (pin "4") (pinfunction "V-_4") (pintype "power_in"))
      (node (ref "IC12") (pin "5") (pinfunction "GND_5") (pintype "input"))
      (node (ref "IC2") (pin "3") (pinfunction "+IN_3") (pintype "input"))
      (node (ref "IC2") (pin "4") (pinfunction "V-_4") (pintype "power_in"))
      (node (ref "IC3") (pin "21") (pinfunction "AGND_21") (pintype "power_in"))
      (node (ref "IC3") (pin "3") (pinfunction "GND_3") (pintype "power_in"))
      (node (ref "IC3") (pin "5") (pinfunction "GND_5") (pintype "power_in"))
      (node (ref "IC4") (pin "3") (pinfunction "+IN_3") (pintype "input"))
      (node (ref "IC4") (pin "4") (pinfunction "V-_4") (pintype "power_in"))
      (node (ref "IC5") (pin "3") (pinfunction "+IN_3") (pintype "input"))
      (node (ref "IC5") (pin "4") (pinfunction "V-_4") (pintype "power_in"))
      (node (ref "IC6") (pin "3") (pinfunction "+IN_3") (pintype "input"))
      (node (ref "IC6") (pin "4") (pinfunction "V-_4") (pintype "power_in"))
      (node (ref "IC7") (pin "3") (pinfunction "+IN_3") (pintype "input"))
      (node (ref "IC7") (pin "4") (pinfunction "V-_4") (pintype "power_in"))
      (node (ref "IC8") (pin "3") (pinfunction "+IN_3") (pintype "input"))
      (node (ref "IC8") (pin "4") (pinfunction "V-_4") (pintype "power_in"))
      (node (ref "IC9") (pin "3") (pinfunction "+IN_3") (pintype "input"))
      (node (ref "IC9") (pin "4") (pinfunction "V-_4") (pintype "power_in"))
      (node (ref "ISP1") (pin "6") (pinfunction "6_6") (pintype "passive"))
      (node (ref "JP1") (pin "1") (pinfunction "1_1") (pintype "passive"))
      (node (ref "R12") (pin "1") (pinfunction "1_1") (pintype "passive"))
      (node (ref "R13") (pin "1") (pinfunction "1_1") (pintype "passive"))
      (node (ref "R16") (pin "1") (pinfunction "1_1") (pintype "passive"))
      (node (ref "R20") (pin "1") (pinfunction "1_1") (pintype "passive"))
      (node (ref "R23") (pin "1") (pinfunction "1_1") (pintype "passive"))
      (node (ref "R27") (pin "1") (pinfunction "1_1") (pintype "passive"))
      (node (ref "R30") (pin "1") (pinfunction "1_1") (pintype "passive"))
      (node (ref "R34") (pin "1") (pinfunction "1_1") (pintype "passive"))
      (node (ref "R37") (pin "1") (pinfunction "1_1") (pintype "passive"))
      (node (ref "R41") (pin "1") (pinfunction "1_1") (pintype "passive"))
      (node (ref "R44") (pin "1") (pinfunction "1_1") (pintype "passive"))
      (node (ref "R48") (pin "1") (pinfunction "1_1") (pintype "passive"))
      (node (ref "R5") (pin "1") (pinfunction "1_1") (pintype "passive"))
      (node (ref "R51") (pin "1") (pinfunction "1_1") (pintype "passive"))
      (node (ref "R53") (pin "1") (pinfunction "1_1") (pintype "passive"))
      (node (ref "R56") (pin "1") (pinfunction "1_1") (pintype "passive"))
      (node (ref "R8") (pin "1") (pinfunction "1_1") (pintype "passive"))
      (node (ref "U$1") (pin "GND") (pinfunction "GND_GND") (pintype "bidirectional"))
      (node (ref "U$1") (pin "MTN1") (pinfunction "MTN2_MTN1") (pintype "bidirectional"))
      (node (ref "U$1") (pin "MTN2") (pinfunction "MTN3_MTN2") (pintype "bidirectional"))
      (node (ref "U$1") (pin "MTN3") (pinfunction "MTN1_MTN3") (pintype "bidirectional"))
      (node (ref "U$1") (pin "MTN4") (pinfunction "MTN4_MTN4") (pintype "bidirectional"))
      (node (ref "U3") (pin "7") (pinfunction "7_7") (pintype "bidirectional"))
      (node (ref "U3") (pin "8") (pinfunction "8_8") (pintype "bidirectional"))
      (node (ref "X1") (pin "2") (pinfunction "SK_2") (pintype "passive"))
      (node (ref "X2") (pin "2") (pinfunction "SK_2") (pintype "passive"))
      (node (ref "X3") (pin "2") (pinfunction "SK_2") (pintype "passive"))
      (node (ref "X4") (pin "2") (pinfunction "SK_2") (pintype "passive"))
      (node (ref "X5") (pin "2") (pinfunction "SK_2") (pintype "passive"))
      (node (ref "X6") (pin "2") (pinfunction "SK_2") (pintype "passive"))
      (node (ref "X7") (pin "2") (pinfunction "SK_2") (pintype "passive"))
      (node (ref "X8") (pin "2") (pinfunction "SK_2") (pintype "passive"))
    )
    (net (code "30") (name "Net-(C5-Pad2)") (class "Default")
      (node (ref "C5") (pin "2") (pinfunction "2_2") (pintype "passive"))
      (node (ref "R4") (pin "2") (pinfunction "2_2") (pintype "passive"))
    )
    (net (code "31") (name "Net-(C16-Pad2)") (class "Default")
      (node (ref "C16") (pin "2") (pinfunction "2_2") (pintype "passive"))
      (node (ref "R11") (pin "2") (pinfunction "2_2") (pintype "passive"))
    )
    (net (code "32") (name "Net-(C22-Pad2)") (class "Default")
      (node (ref "C22") (pin "2") (pinfunction "2_2") (pintype "passive"))
      (node (ref "R19") (pin "2") (pinfunction "2_2") (pintype "passive"))
    )
    (net (code "33") (name "Net-(C28-Pad2)") (class "Default")
      (node (ref "C28") (pin "2") (pinfunction "2_2") (pintype "passive"))
      (node (ref "R26") (pin "2") (pinfunction "2_2") (pintype "passive"))
    )
    (net (code "34") (name "Net-(C34-Pad2)") (class "Default")
      (node (ref "C34") (pin "2") (pinfunction "2_2") (pintype "passive"))
      (node (ref "R33") (pin "2") (pinfunction "2_2") (pintype "passive"))
    )
    (net (code "35") (name "Net-(C44-Pad2)") (class "Default")
      (node (ref "C44") (pin "2") (pinfunction "2_2") (pintype "passive"))
      (node (ref "R40") (pin "2") (pinfunction "2_2") (pintype "passive"))
    )
    (net (code "36") (name "Net-(C50-Pad2)") (class "Default")
      (node (ref "C50") (pin "2") (pinfunction "2_2") (pintype "passive"))
      (node (ref "R47") (pin "2") (pinfunction "2_2") (pintype "passive"))
    )
    (net (code "37") (name "Net-(C56-Pad2)") (class "Default")
      (node (ref "C56") (pin "2") (pinfunction "2_2") (pintype "passive"))
      (node (ref "R59") (pin "2") (pinfunction "2_2") (pintype "passive"))
    )
    (net (code "38") (name "Net-(D1-A)") (class "Default")
      (node (ref "D1") (pin "1") (pinfunction "A_1") (pintype "passive"))
      (node (ref "IC2") (pin "1") (pinfunction "OUT_1") (pintype "output"))
    )
    (net (code "39") (name "Net-(D1-C)") (class "Default")
      (node (ref "D1") (pin "3") (pinfunction "C_3") (pintype "passive"))
      (node (ref "IC2") (pin "5") (pinfunction "+IN_5") (pintype "input"))
      (node (ref "R7") (pin "2") (pinfunction "2_2") (pintype "passive"))
    )
    (net (code "40") (name "Net-(D2-A)") (class "Default")
      (node (ref "D2") (pin "1") (pinfunction "A_1") (pintype "passive"))
      (node (ref "IC4") (pin "1") (pinfunction "OUT_1") (pintype "output"))
    )
    (net (code "41") (name "Net-(D2-C)") (class "Default")
      (node (ref "D2") (pin "3") (pinfunction "C_3") (pintype "passive"))
      (node (ref "IC4") (pin "5") (pinfunction "+IN_5") (pintype "input"))
      (node (ref "R15") (pin "2") (pinfunction "2_2") (pintype "passive"))
    )
    (net (code "42") (name "Net-(D3-A)") (class "Default")
      (node (ref "D3") (pin "1") (pinfunction "A_1") (pintype "passive"))
      (node (ref "IC5") (pin "1") (pinfunction "OUT_1") (pintype "output"))
    )
    (net (code "43") (name "Net-(D3-C)") (class "Default")
      (node (ref "D3") (pin "3") (pinfunction "C_3") (pintype "passive"))
      (node (ref "IC5") (pin "5") (pinfunction "+IN_5") (pintype "input"))
      (node (ref "R22") (pin "2") (pinfunction "2_2") (pintype "passive"))
    )
    (net (code "44") (name "Net-(D4-A)") (class "Default")
      (node (ref "D4") (pin "1") (pinfunction "A_1") (pintype "passive"))
      (node (ref "IC6") (pin "1") (pinfunction "OUT_1") (pintype "output"))
    )
    (net (code "45") (name "Net-(D4-C)") (class "Default")
      (node (ref "D4") (pin "3") (pinfunction "C_3") (pintype "passive"))
      (node (ref "IC6") (pin "5") (pinfunction "+IN_5") (pintype "input"))
      (node (ref "R29") (pin "2") (pinfunction "2_2") (pintype "passive"))
    )
    (net (code "46") (name "Net-(D5-A)") (class "Default")
      (node (ref "D5") (pin "1") (pinfunction "A_1") (pintype "passive"))
      (node (ref "IC7") (pin "1") (pinfunction "OUT_1") (pintype "output"))
    )
    (net (code "47") (name "Net-(D5-C)") (class "Default")
      (node (ref "D5") (pin "3") (pinfunction "C_3") (pintype "passive"))
      (node (ref "IC7") (pin "5") (pinfunction "+IN_5") (pintype "input"))
      (node (ref "R36") (pin "2") (pinfunction "2_2") (pintype "passive"))
    )
    (net (code "48") (name "Net-(D6-A)") (class "Default")
      (node (ref "D6") (pin "1") (pinfunction "A_1") (pintype "passive"))
      (node (ref "IC8") (pin "1") (pinfunction "OUT_1") (pintype "output"))
    )
    (net (code "49") (name "Net-(D6-C)") (class "Default")
      (node (ref "D6") (pin "3") (pinfunction "C_3") (pintype "passive"))
      (node (ref "IC8") (pin "5") (pinfunction "+IN_5") (pintype "input"))
      (node (ref "R43") (pin "2") (pinfunction "2_2") (pintype "passive"))
    )
    (net (code "50") (name "Net-(D7-A)") (class "Default")
      (node (ref "D7") (pin "1") (pinfunction "A_1") (pintype "passive"))
      (node (ref "IC9") (pin "1") (pinfunction "OUT_1") (pintype "output"))
    )
    (net (code "51") (name "Net-(D7-C)") (class "Default")
      (node (ref "D7") (pin "3") (pinfunction "C_3") (pintype "passive"))
      (node (ref "IC9") (pin "5") (pinfunction "+IN_5") (pintype "input"))
      (node (ref "R55") (pin "2") (pinfunction "2_2") (pintype "passive"))
    )
    (net (code "52") (name "Net-(D8-A)") (class "Default")
      (node (ref "D8") (pin "1") (pinfunction "A_1") (pintype "passive"))
      (node (ref "IC10") (pin "1") (pinfunction "OUT_1") (pintype "output"))
    )
    (net (code "53") (name "Net-(D8-C)") (class "Default")
      (node (ref "D8") (pin "3") (pinfunction "C_3") (pintype "passive"))
      (node (ref "IC10") (pin "5") (pinfunction "+IN_5") (pintype "input"))
      (node (ref "R50") (pin "2") (pinfunction "2_2") (pintype "passive"))
    )
    (net (code "54") (name "Net-(IC2A--IN)") (class "Default")
      (node (ref "IC2") (pin "2") (pinfunction "-IN_2") (pintype "input"))
      (node (ref "R6") (pin "2") (pinfunction "2_2") (pintype "passive"))
      (node (ref "R7") (pin "1") (pinfunction "1_1") (pintype "passive"))
    )
    (net (code "55") (name "Net-(IC2B--IN)") (class "Default")
      (node (ref "C16") (pin "1") (pinfunction "1_1") (pintype "passive"))
      (node (ref "IC2") (pin "6") (pinfunction "-IN_6") (pintype "input"))
      (node (ref "R9") (pin "1") (pinfunction "1_1") (pintype "passive"))
    )
    (net (code "56") (name "Net-(IC2B-OUT)") (class "Default")
      (node (ref "IC2") (pin "7") (pinfunction "OUT_7") (pintype "output"))
      (node (ref "R10") (pin "1") (pinfunction "1_1") (pintype "passive"))
      (node (ref "R9") (pin "2") (pinfunction "2_2") (pintype "passive"))
    )
    (net (code "57") (name "Net-(IC3-AREF)") (class "Default")
      (node (ref "C9") (pin "1") (pinfunction "1_1") (pintype "passive"))
      (node (ref "IC3") (pin "20") (pinfunction "AREF_20") (pintype "passive"))
    )
    (net (code "58") (name "Net-(IC3-PB6(XTAL1{slash}TOSC1{slash}PCINT6))") (class "Default")
      (node (ref "C11") (pin "1") (pinfunction "1_1") (pintype "passive"))
      (node (ref "IC3") (pin "7") (pinfunction "PB6(XTAL1/TOSC1/PCINT6)_7") (pintype "bidirectional"))
      (node (ref "Y1") (pin "1") (pinfunction "1_1") (pintype "passive"))
    )
    (net (code "59") (name "Net-(IC3-PB7(XTAL2{slash}TOSC2{slash}PCINT7))") (class "Default")
      (node (ref "C10") (pin "1") (pinfunction "1_1") (pintype "passive"))
      (node (ref "IC3") (pin "8") (pinfunction "PB7(XTAL2/TOSC2/PCINT7)_8") (pintype "bidirectional"))
      (node (ref "Y1") (pin "2") (pinfunction "2_2") (pintype "passive"))
    )
    (net (code "60") (name "Net-(IC4A--IN)") (class "Default")
      (node (ref "IC4") (pin "2") (pinfunction "-IN_2") (pintype "input"))
      (node (ref "R14") (pin "2") (pinfunction "2_2") (pintype "passive"))
      (node (ref "R15") (pin "1") (pinfunction "1_1") (pintype "passive"))
    )
    (net (code "61") (name "Net-(IC4B--IN)") (class "Default")
      (node (ref "C22") (pin "1") (pinfunction "1_1") (pintype "passive"))
      (node (ref "IC4") (pin "6") (pinfunction "-IN_6") (pintype "input"))
      (node (ref "R17") (pin "1") (pinfunction "1_1") (pintype "passive"))
    )
    (net (code "62") (name "Net-(IC4B-OUT)") (class "Default")
      (node (ref "IC4") (pin "7") (pinfunction "OUT_7") (pintype "output"))
      (node (ref "R17") (pin "2") (pinfunction "2_2") (pintype "passive"))
      (node (ref "R18") (pin "1") (pinfunction "1_1") (pintype "passive"))
    )
    (net (code "63") (name "Net-(IC5A--IN)") (class "Default")
      (node (ref "IC5") (pin "2") (pinfunction "-IN_2") (pintype "input"))
      (node (ref "R21") (pin "2") (pinfunction "2_2") (pintype "passive"))
      (node (ref "R22") (pin "1") (pinfunction "1_1") (pintype "passive"))
    )
    (net (code "64") (name "Net-(IC5B--IN)") (class "Default")
      (node (ref "C28") (pin "1") (pinfunction "1_1") (pintype "passive"))
      (node (ref "IC5") (pin "6") (pinfunction "-IN_6") (pintype "input"))
      (node (ref "R24") (pin "1") (pinfunction "1_1") (pintype "passive"))
    )
    (net (code "65") (name "Net-(IC5B-OUT)") (class "Default")
      (node (ref "IC5") (pin "7") (pinfunction "OUT_7") (pintype "output"))
      (node (ref "R24") (pin "2") (pinfunction "2_2") (pintype "passive"))
      (node (ref "R25") (pin "1") (pinfunction "1_1") (pintype "passive"))
    )
    (net (code "66") (name "Net-(IC6A--IN)") (class "Default")
      (node (ref "IC6") (pin "2") (pinfunction "-IN_2") (pintype "input"))
      (node (ref "R28") (pin "2") (pinfunction "2_2") (pintype "passive"))
      (node (ref "R29") (pin "1") (pinfunction "1_1") (pintype "passive"))
    )
    (net (code "67") (name "Net-(IC6B--IN)") (class "Default")
      (node (ref "C34") (pin "1") (pinfunction "1_1") (pintype "passive"))
      (node (ref "IC6") (pin "6") (pinfunction "-IN_6") (pintype "input"))
      (node (ref "R31") (pin "1") (pinfunction "1_1") (pintype "passive"))
    )
    (net (code "68") (name "Net-(IC6B-OUT)") (class "Default")
      (node (ref "IC6") (pin "7") (pinfunction "OUT_7") (pintype "output"))
      (node (ref "R31") (pin "2") (pinfunction "2_2") (pintype "passive"))
      (node (ref "R32") (pin "1") (pinfunction "1_1") (pintype "passive"))
    )
    (net (code "69") (name "Net-(IC7A--IN)") (class "Default")
      (node (ref "IC7") (pin "2") (pinfunction "-IN_2") (pintype "input"))
      (node (ref "R35") (pin "2") (pinfunction "2_2") (pintype "passive"))
      (node (ref "R36") (pin "1") (pinfunction "1_1") (pintype "passive"))
    )
    (net (code "70") (name "Net-(IC7B--IN)") (class "Default")
      (node (ref "C44") (pin "1") (pinfunction "1_1") (pintype "passive"))
      (node (ref "IC7") (pin "6") (pinfunction "-IN_6") (pintype "input"))
      (node (ref "R38") (pin "1") (pinfunction "1_1") (pintype "passive"))
    )
    (net (code "71") (name "Net-(IC7B-OUT)") (class "Default")
      (node (ref "IC7") (pin "7") (pinfunction "OUT_7") (pintype "output"))
      (node (ref "R38") (pin "2") (pinfunction "2_2") (pintype "passive"))
      (node (ref "R39") (pin "1") (pinfunction "1_1") (pintype "passive"))
    )
    (net (code "72") (name "Net-(IC8A--IN)") (class "Default")
      (node (ref "IC8") (pin "2") (pinfunction "-IN_2") (pintype "input"))
      (node (ref "R42") (pin "2") (pinfunction "2_2") (pintype "passive"))
      (node (ref "R43") (pin "1") (pinfunction "1_1") (pintype "passive"))
    )
    (net (code "73") (name "Net-(IC8B--IN)") (class "Default")
      (node (ref "C50") (pin "1") (pinfunction "1_1") (pintype "passive"))
      (node (ref "IC8") (pin "6") (pinfunction "-IN_6") (pintype "input"))
      (node (ref "R45") (pin "1") (pinfunction "1_1") (pintype "passive"))
    )
    (net (code "74") (name "Net-(IC8B-OUT)") (class "Default")
      (node (ref "IC8") (pin "7") (pinfunction "OUT_7") (pintype "output"))
      (node (ref "R45") (pin "2") (pinfunction "2_2") (pintype "passive"))
      (node (ref "R46") (pin "1") (pinfunction "1_1") (pintype "passive"))
    )
    (net (code "75") (name "Net-(IC9A--IN)") (class "Default")
      (node (ref "IC9") (pin "2") (pinfunction "-IN_2") (pintype "input"))
      (node (ref "R54") (pin "2") (pinfunction "2_2") (pintype "passive"))
      (node (ref "R55") (pin "1") (pinfunction "1_1") (pintype "passive"))
    )
    (net (code "76") (name "Net-(IC9B--IN)") (class "Default")
      (node (ref "C5") (pin "1") (pinfunction "1_1") (pintype "passive"))
      (node (ref "IC9") (pin "6") (pinfunction "-IN_6") (pintype "input"))
      (node (ref "R57") (pin "1") (pinfunction "1_1") (pintype "passive"))
    )
    (net (code "77") (name "Net-(IC9B-OUT)") (class "Default")
      (node (ref "IC9") (pin "7") (pinfunction "OUT_7") (pintype "output"))
      (node (ref "R57") (pin "2") (pinfunction "2_2") (pintype "passive"))
      (node (ref "R60") (pin "1") (pinfunction "1_1") (pintype "passive"))
    )
    (net (code "78") (name "Net-(IC10A--IN)") (class "Default")
      (node (ref "IC10") (pin "2") (pinfunction "-IN_2") (pintype "input"))
      (node (ref "R49") (pin "2") (pinfunction "2_2") (pintype "passive"))
      (node (ref "R50") (pin "1") (pinfunction "1_1") (pintype "passive"))
    )
    (net (code "79") (name "Net-(IC10B--IN)") (class "Default")
      (node (ref "C56") (pin "1") (pinfunction "1_1") (pintype "passive"))
      (node (ref "IC10") (pin "6") (pinfunction "-IN_6") (pintype "input"))
      (node (ref "R52") (pin "1") (pinfunction "1_1") (pintype "passive"))
    )
    (net (code "80") (name "Net-(IC10B-OUT)") (class "Default")
      (node (ref "IC10") (pin "7") (pinfunction "OUT_7") (pintype "output"))
      (node (ref "R52") (pin "2") (pinfunction "2_2") (pintype "passive"))
      (node (ref "R58") (pin "1") (pinfunction "1_1") (pintype "passive"))
    )
    (net (code "81") (name "Net-(LED1-PadC)") (class "Default")
      (node (ref "LED1") (pin "C") (pinfunction "C_C") (pintype "passive"))
      (node (ref "R13") (pin "2") (pinfunction "2_2") (pintype "passive"))
    )
    (net (code "82") (name "Net-(R1-Pad1)") (class "Default")
      (node (ref "R1") (pin "1") (pinfunction "1_1") (pintype "passive"))
      (node (ref "U$1") (pin "D+") (pinfunction "D+_D+") (pintype "bidirectional"))
    )
    (net (code "83") (name "Net-(R2-Pad1)") (class "Default")
      (node (ref "R2") (pin "1") (pinfunction "1_1") (pintype "passive"))
      (node (ref "R3") (pin "1") (pinfunction "1_1") (pintype "passive"))
      (node (ref "U$1") (pin "D-") (pinfunction "D-_D-") (pintype "bidirectional"))
    )
    (net (code "84") (name "Net-(X1A-SK)") (class "Default")
      (node (ref "C15") (pin "1") (pinfunction "1_1") (pintype "passive"))
      (node (ref "R5") (pin "2") (pinfunction "2_2") (pintype "passive"))
      (node (ref "R6") (pin "1") (pinfunction "1_1") (pintype "passive"))
      (node (ref "X1") (pin "1") (pinfunction "SK_1") (pintype "passive"))
    )
    (net (code "85") (name "Net-(X2A-SK)") (class "Default")
      (node (ref "C21") (pin "1") (pinfunction "1_1") (pintype "passive"))
      (node (ref "R12") (pin "2") (pinfunction "2_2") (pintype "passive"))
      (node (ref "R14") (pin "1") (pinfunction "1_1") (pintype "passive"))
      (node (ref "X2") (pin "1") (pinfunction "SK_1") (pintype "passive"))
    )
    (net (code "86") (name "Net-(X3A-SK)") (class "Default")
      (node (ref "C27") (pin "1") (pinfunction "1_1") (pintype "passive"))
      (node (ref "R20") (pin "2") (pinfunction "2_2") (pintype "passive"))
      (node (ref "R21") (pin "1") (pinfunction "1_1") (pintype "passive"))
      (node (ref "X3") (pin "1") (pinfunction "SK_1") (pintype "passive"))
    )
    (net (code "87") (name "Net-(X4A-SK)") (class "Default")
      (node (ref "C33") (pin "1") (pinfunction "1_1") (pintype "passive"))
      (node (ref "R27") (pin "2") (pinfunction "2_2") (pintype "passive"))
      (node (ref "R28") (pin "1") (pinfunction "1_1") (pintype "passive"))
      (node (ref "X4") (pin "1") (pinfunction "SK_1") (pintype "passive"))
    )
    (net (code "88") (name "Net-(X5A-SK)") (class "Default")
      (node (ref "C39") (pin "1") (pinfunction "1_1") (pintype "passive"))
      (node (ref "R34") (pin "2") (pinfunction "2_2") (pintype "passive"))
      (node (ref "R35") (pin "1") (pinfunction "1_1") (pintype "passive"))
      (node (ref "X5") (pin "1") (pinfunction "SK_1") (pintype "passive"))
    )
    (net (code "89") (name "Net-(X6A-SK)") (class "Default")
      (node (ref "C49") (pin "1") (pinfunction "1_1") (pintype "passive"))
      (node (ref "R41") (pin "2") (pinfunction "2_2") (pintype "passive"))
      (node (ref "R42") (pin "1") (pinfunction "1_1") (pintype "passive"))
      (node (ref "X6") (pin "1") (pinfunction "SK_1") (pintype "passive"))
    )
    (net (code "90") (name "Net-(X7A-SK)") (class "Default")
      (node (ref "C4") (pin "1") (pinfunction "1_1") (pintype "passive"))
      (node (ref "R53") (pin "2") (pinfunction "2_2") (pintype "passive"))
      (node (ref "R54") (pin "1") (pinfunction "1_1") (pintype "passive"))
      (node (ref "X7") (pin "1") (pinfunction "SK_1") (pintype "passive"))
    )
    (net (code "91") (name "Net-(X8A-SK)") (class "Default")
      (node (ref "C55") (pin "1") (pinfunction "1_1") (pintype "passive"))
      (node (ref "R48") (pin "2") (pinfunction "2_2") (pintype "passive"))
      (node (ref "R49") (pin "1") (pinfunction "1_1") (pintype "passive"))
      (node (ref "X8") (pin "1") (pinfunction "SK_1") (pintype "passive"))
    )
    (net (code "92") (name "VCC") (class "Default")
      (node (ref "C1") (pin "1") (pinfunction "1_1") (pintype "passive"))
      (node (ref "C12") (pin "1") (pinfunction "1_1") (pintype "passive"))
      (node (ref "C13") (pin "1") (pinfunction "1_1") (pintype "passive"))
      (node (ref "C19") (pin "1") (pinfunction "1_1") (pintype "passive"))
      (node (ref "C25") (pin "1") (pinfunction "1_1") (pintype "passive"))
      (node (ref "C3") (pin "1") (pinfunction "1_1") (pintype "passive"))
      (node (ref "C31") (pin "1") (pinfunction "1_1") (pintype "passive"))
      (node (ref "C37") (pin "1") (pinfunction "1_1") (pintype "passive"))
      (node (ref "C42") (pin "1") (pinfunction "1_1") (pintype "passive"))
      (node (ref "C47") (pin "1") (pinfunction "1_1") (pintype "passive"))
      (node (ref "C53") (pin "1") (pinfunction "1_1") (pintype "passive"))
      (node (ref "C57") (pin "1") (pinfunction "1_1") (pintype "passive"))
      (node (ref "C8") (pin "1") (pinfunction "1_1") (pintype "passive"))
      (node (ref "IC1") (pin "2") (pinfunction "OUT_2") (pintype "output"))
      (node (ref "IC1") (pin "4") (pinfunction "OUT_4") (pintype "output"))
      (node (ref "IC10") (pin "8") (pinfunction "V+_8") (pintype "power_in"))
      (node (ref "IC12") (pin "8") (pinfunction "VCC_8") (pintype "input"))
      (node (ref "IC2") (pin "8") (pinfunction "V+_8") (pintype "power_in"))
      (node (ref "IC3") (pin "18") (pinfunction "AVCC_18") (pintype "passive"))
      (node (ref "IC3") (pin "4") (pinfunction "VCC_4") (pintype "power_in"))
      (node (ref "IC3") (pin "6") (pinfunction "VCC_6") (pintype "power_in"))
      (node (ref "IC4") (pin "8") (pinfunction "V+_8") (pintype "power_in"))
      (node (ref "IC5") (pin "8") (pinfunction "V+_8") (pintype "power_in"))
      (node (ref "IC6") (pin "8") (pinfunction "V+_8") (pintype "power_in"))
      (node (ref "IC7") (pin "8") (pinfunction "V+_8") (pintype "power_in"))
      (node (ref "IC8") (pin "8") (pinfunction "V+_8") (pintype "power_in"))
      (node (ref "IC9") (pin "8") (pinfunction "V+_8") (pintype "power_in"))
      (node (ref "ISP1") (pin "2") (pinfunction "2_2") (pintype "passive"))
      (node (ref "JP1") (pin "4") (pinfunction "4_4") (pintype "passive"))
      (node (ref "R3") (pin "2") (pinfunction "2_2") (pintype "passive"))
    )
    (net (code "93") (name "unconnected-(U$1-PadID)") (class "Default")
      (node (ref "U$1") (pin "ID") (pinfunction "ID_ID") (pintype "bidirectional"))
    )
    (net (code "94") (name "unconnected-(U3-Pad3)") (class "Default")
      (node (ref "U3") (pin "3") (pinfunction "3_3") (pintype "bidirectional"))
    )
    (net (code "95") (name "unconnected-(U3-Pad6)") (class "Default")
      (node (ref "U3") (pin "6") (pinfunction "6_6") (pintype "bidirectional"))
    )
  )
)
